# PowerSupply.net
KiCad netlist of a schematic drawn in Altium Designer
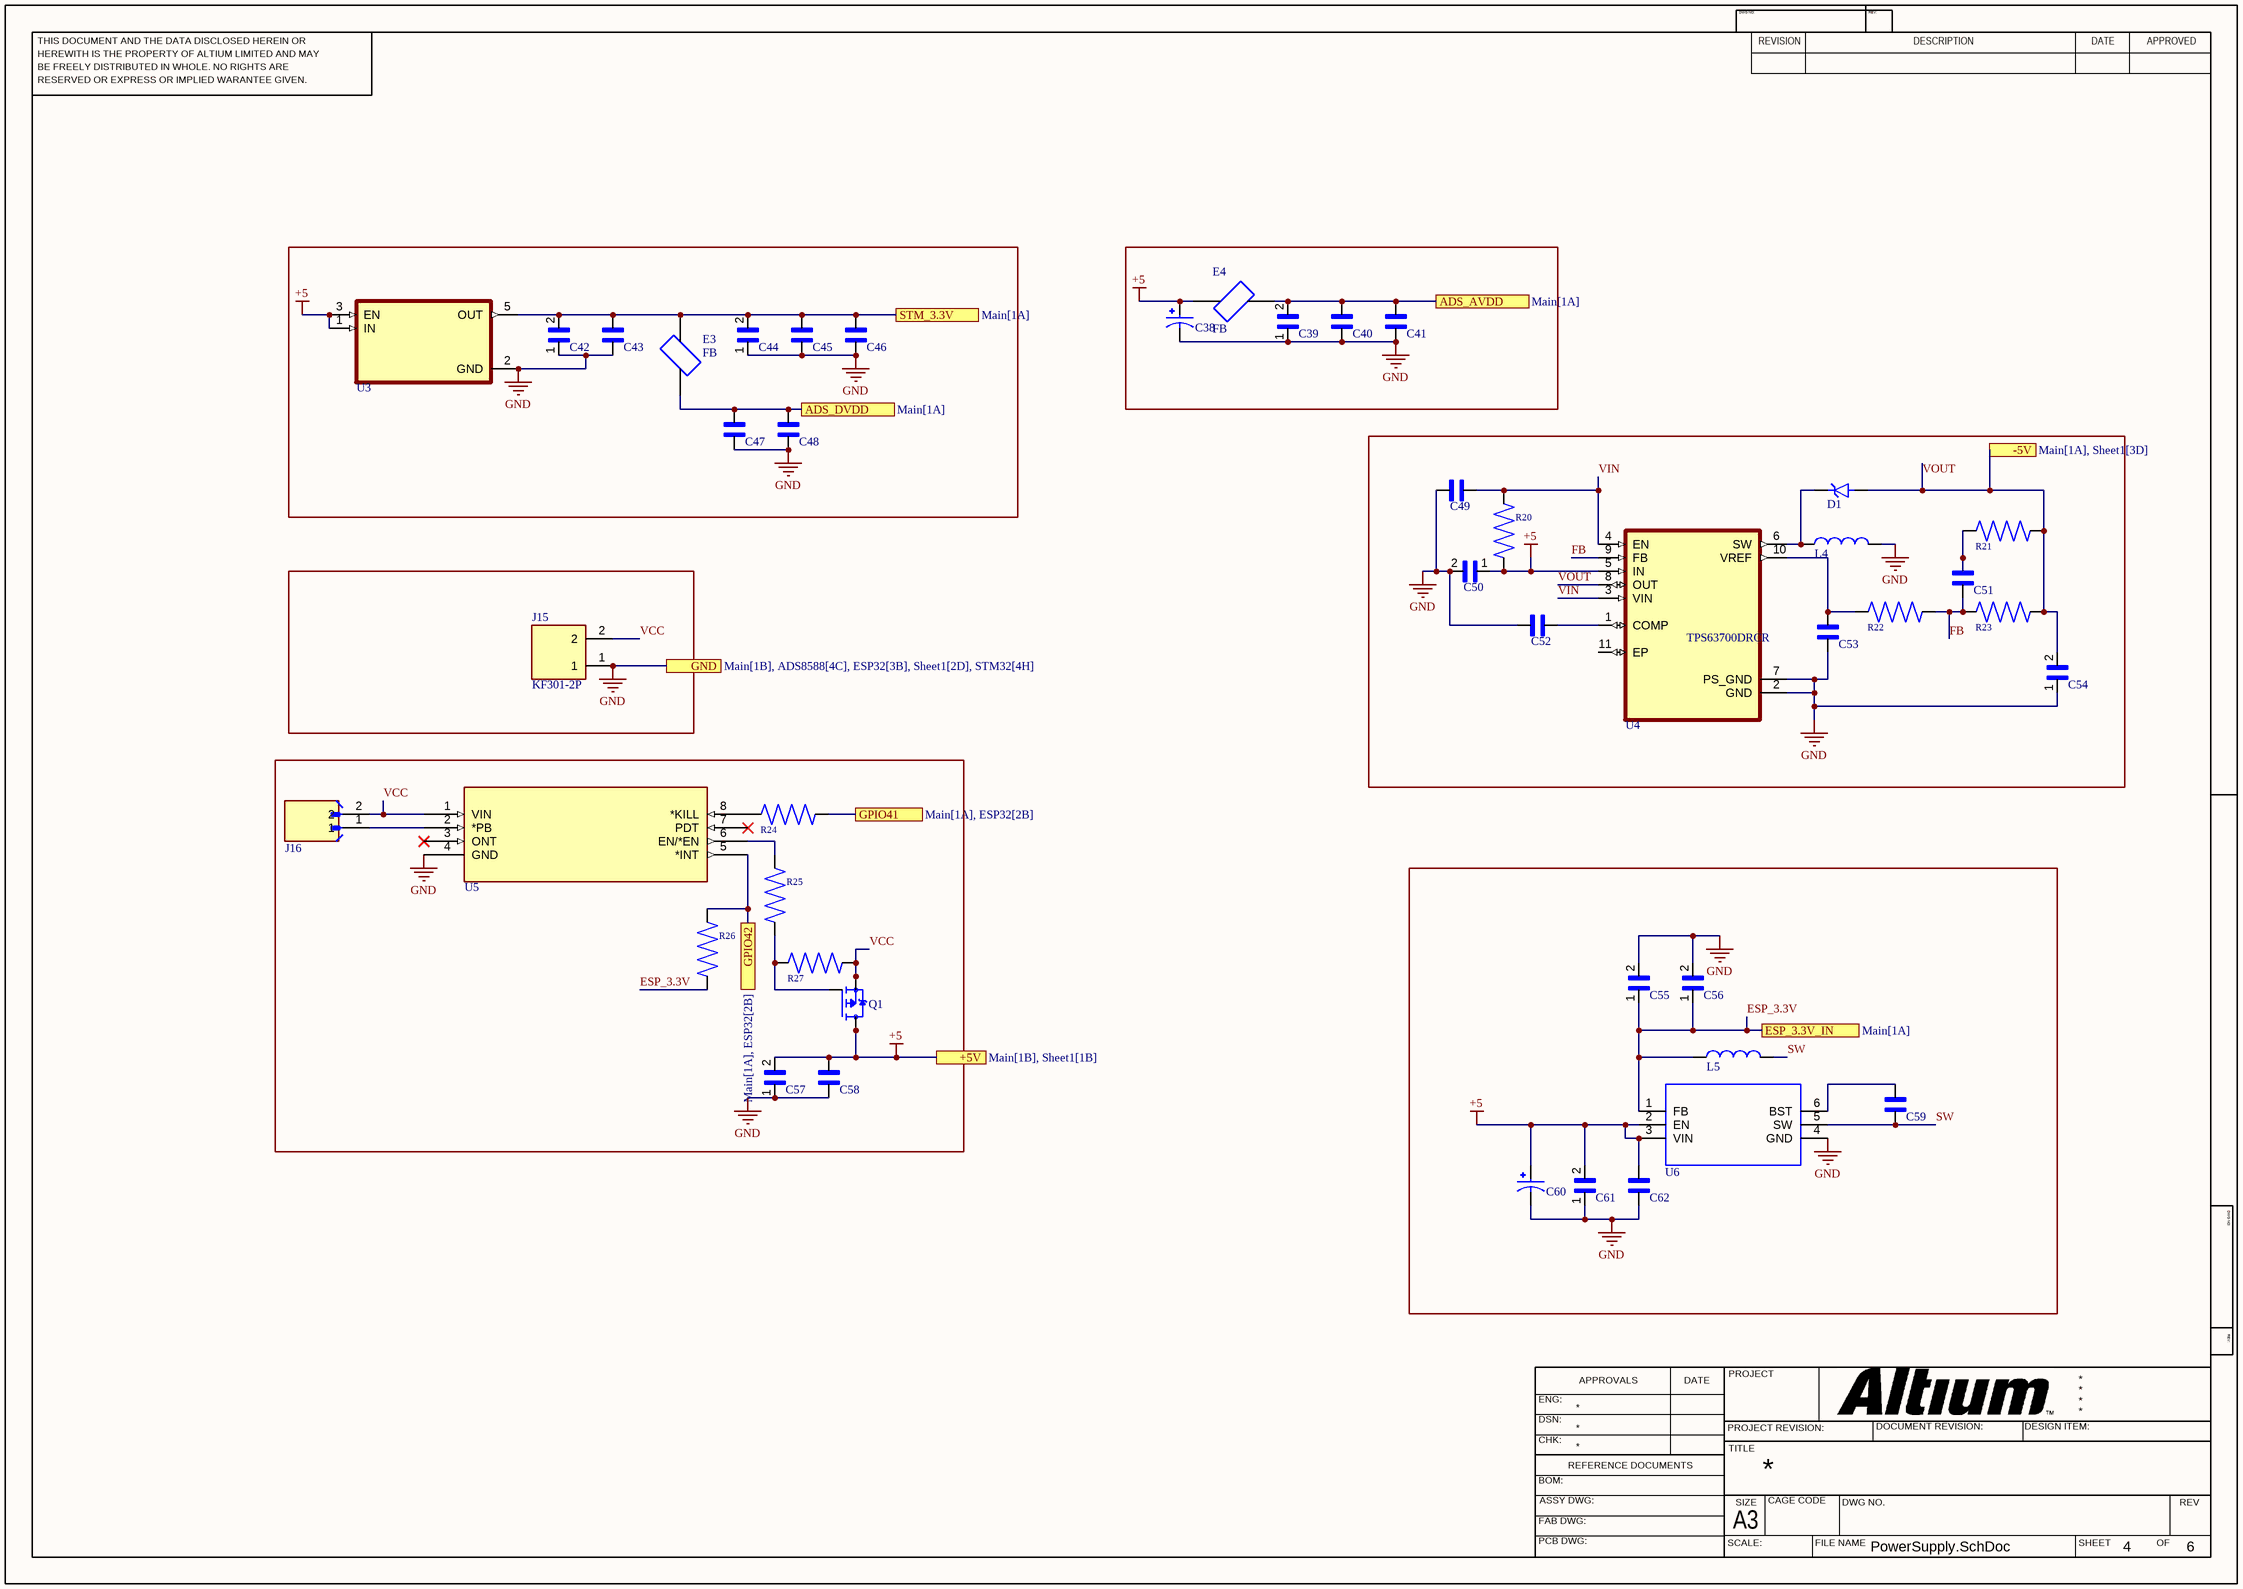
[diagram p0: PowerSupply.SchDoc]

(export (version "E")
  (design (tool "Eeschema 10.0.6"))
  (components
    (comp (ref "C38")
      (value "100 uF")
      (footprint "100 uF")
      (fields (field (name "MF") "Panasonic") (field (name "MP") "16SVPG100M"))
      (libsource (lib "ESP32-S3-WROOM-1-N16R8") (part "100 uF"))
    )
    (comp (ref "C39")
      (value "C2012X7R1H104K085AA")
      (footprint "CAPC2012X100N")
      (description "0.1 ÂµF Â±10% 50V Ceramic Capacitor X7R 0805 (2012 Metric)")
      (fields (field (name "MF") "TDK") (field (name "DIGI-KEY_PART_NUMBER") "445-7534-1-ND"))
      (libsource (lib "ESP32-S3-WROOM-1-N16R8") (part "C2012X7R1H104K085AA"))
    )
    (comp (ref "C40")
      (value "CAP603")
      (footprint "CAP603")
      (description "0.1 ÂµF Â±5% 10V Ceramic Capacitor X7R 0603 (1608 Metric)")
      (fields (field (name "MF") "Vishay") (field (name "MP") "VJ0603Y104JXQCW1BC"))
      (libsource (lib "ESP32-S3-WROOM-1-N16R8") (part "CAP603"))
    )
    (comp (ref "C41")
      (value "CAP603")
      (footprint "CAP603")
      (description "0.1 ÂµF Â±5% 10V Ceramic Capacitor X7R 0603 (1608 Metric)")
      (fields (field (name "MF") "Vishay") (field (name "MP") "VJ0603Y104JXQCW1BC"))
      (libsource (lib "ESP32-S3-WROOM-1-N16R8") (part "CAP603"))
    )
    (comp (ref "C42")
      (value "C2012X7R1H104K085AA")
      (footprint "CAPC2012X100N")
      (description "0.1 ÂµF Â±10% 50V Ceramic Capacitor X7R 0805 (2012 Metric)")
      (fields (field (name "MF") "TDK") (field (name "DIGI-KEY_PART_NUMBER") "445-7534-1-ND"))
      (libsource (lib "ESP32-S3-WROOM-1-N16R8") (part "C2012X7R1H104K085AA"))
    )
    (comp (ref "C43")
      (value "CAP603")
      (footprint "CAP603")
      (description "0.1 ÂµF Â±5% 10V Ceramic Capacitor X7R 0603 (1608 Metric)")
      (fields (field (name "MF") "Vishay") (field (name "MP") "VJ0603Y104JXQCW1BC"))
      (libsource (lib "ESP32-S3-WROOM-1-N16R8") (part "CAP603"))
    )
    (comp (ref "C44")
      (value "C2012X7R1H104K085AA")
      (footprint "CAPC2012X100N")
      (description "0.1 ÂµF Â±10% 50V Ceramic Capacitor X7R 0805 (2012 Metric)")
      (fields (field (name "MF") "TDK") (field (name "DIGI-KEY_PART_NUMBER") "445-7534-1-ND"))
      (libsource (lib "ESP32-S3-WROOM-1-N16R8") (part "C2012X7R1H104K085AA"))
    )
    (comp (ref "C45")
      (value "CAP603")
      (footprint "CAP603")
      (description "0.1 ÂµF Â±5% 10V Ceramic Capacitor X7R 0603 (1608 Metric)")
      (fields (field (name "MF") "Vishay") (field (name "MP") "VJ0603Y104JXQCW1BC"))
      (libsource (lib "ESP32-S3-WROOM-1-N16R8") (part "CAP603"))
    )
    (comp (ref "C46")
      (value "CAP603")
      (footprint "CAP603")
      (description "0.1 ÂµF Â±5% 10V Ceramic Capacitor X7R 0603 (1608 Metric)")
      (fields (field (name "MF") "Vishay") (field (name "MP") "VJ0603Y104JXQCW1BC"))
      (libsource (lib "ESP32-S3-WROOM-1-N16R8") (part "CAP603"))
    )
    (comp (ref "C47")
      (value "CAP603")
      (footprint "CAP603")
      (description "0.1 ÂµF Â±5% 10V Ceramic Capacitor X7R 0603 (1608 Metric)")
      (fields (field (name "MF") "Vishay") (field (name "MP") "VJ0603Y104JXQCW1BC"))
      (libsource (lib "ESP32-S3-WROOM-1-N16R8") (part "CAP603"))
    )
    (comp (ref "C48")
      (value "CAP603")
      (footprint "CAP603")
      (description "0.1 ÂµF Â±5% 10V Ceramic Capacitor X7R 0603 (1608 Metric)")
      (fields (field (name "MF") "Vishay") (field (name "MP") "VJ0603Y104JXQCW1BC"))
      (libsource (lib "ESP32-S3-WROOM-1-N16R8") (part "CAP603"))
    )
    (comp (ref "C49")
      (value "CAP603")
      (footprint "CAP603")
      (description "0.1 ÂµF Â±5% 10V Ceramic Capacitor X7R 0603 (1608 Metric)")
      (fields (field (name "MF") "Vishay") (field (name "MP") "VJ0603Y104JXQCW1BC"))
      (libsource (lib "") (part "CAP603_1"))
    )
    (comp (ref "C50")
      (value "C2012X7R1H104K085AA")
      (footprint "CAPC2012X100N")
      (description "0.1 ÂµF Â±10% 50V Ceramic Capacitor X7R 0805 (2012 Metric)")
      (fields (field (name "MF") "TDK") (field (name "DIGI-KEY_PART_NUMBER") "445-7534-1-ND"))
      (libsource (lib "") (part "C2012X7R1H104K085AA_1"))
    )
    (comp (ref "C51")
      (value "CAP603")
      (footprint "CAP603")
      (description "0.1 ÂµF Â±5% 10V Ceramic Capacitor X7R 0603 (1608 Metric)")
      (fields (field (name "MF") "Vishay") (field (name "MP") "VJ0603Y104JXQCW1BC"))
      (libsource (lib "ESP32-S3-WROOM-1-N16R8") (part "CAP603"))
    )
    (comp (ref "C52")
      (value "CAP603")
      (footprint "CAP603")
      (description "0.1 ÂµF Â±5% 10V Ceramic Capacitor X7R 0603 (1608 Metric)")
      (fields (field (name "MF") "Vishay") (field (name "MP") "VJ0603Y104JXQCW1BC"))
      (libsource (lib "") (part "CAP603_1"))
    )
    (comp (ref "C53")
      (value "CAP603")
      (footprint "CAP603")
      (description "0.1 ÂµF Â±5% 10V Ceramic Capacitor X7R 0603 (1608 Metric)")
      (fields (field (name "MF") "Vishay") (field (name "MP") "VJ0603Y104JXQCW1BC"))
      (libsource (lib "ESP32-S3-WROOM-1-N16R8") (part "CAP603"))
    )
    (comp (ref "C54")
      (value "C2012X7R1H104K085AA")
      (footprint "CAPC2012X100N")
      (description "0.1 ÂµF Â±10% 50V Ceramic Capacitor X7R 0805 (2012 Metric)")
      (fields (field (name "MF") "TDK") (field (name "DIGI-KEY_PART_NUMBER") "445-7534-1-ND"))
      (libsource (lib "ESP32-S3-WROOM-1-N16R8") (part "C2012X7R1H104K085AA"))
    )
    (comp (ref "C55")
      (value "C2012X7R1H104K085AA")
      (footprint "CAPC2012X100N")
      (description "0.1 ÂµF Â±10% 50V Ceramic Capacitor X7R 0805 (2012 Metric)")
      (fields (field (name "MF") "TDK") (field (name "DIGI-KEY_PART_NUMBER") "445-7534-1-ND"))
      (libsource (lib "ESP32-S3-WROOM-1-N16R8") (part "C2012X7R1H104K085AA"))
    )
    (comp (ref "C56")
      (value "C2012X7R1H104K085AA")
      (footprint "CAPC2012X100N")
      (description "0.1 ÂµF Â±10% 50V Ceramic Capacitor X7R 0805 (2012 Metric)")
      (fields (field (name "MF") "TDK") (field (name "DIGI-KEY_PART_NUMBER") "445-7534-1-ND"))
      (libsource (lib "ESP32-S3-WROOM-1-N16R8") (part "C2012X7R1H104K085AA"))
    )
    (comp (ref "C57")
      (value "C2012X7R1H104K085AA")
      (footprint "CAPC2012X100N")
      (description "0.1 ÂµF Â±10% 50V Ceramic Capacitor X7R 0805 (2012 Metric)")
      (fields (field (name "MF") "TDK") (field (name "DIGI-KEY_PART_NUMBER") "445-7534-1-ND"))
      (libsource (lib "ESP32-S3-WROOM-1-N16R8") (part "C2012X7R1H104K085AA"))
    )
    (comp (ref "C58")
      (value "CAP603")
      (footprint "CAP603")
      (description "0.1 ÂµF Â±5% 10V Ceramic Capacitor X7R 0603 (1608 Metric)")
      (fields (field (name "MF") "Vishay") (field (name "MP") "VJ0603Y104JXQCW1BC"))
      (libsource (lib "ESP32-S3-WROOM-1-N16R8") (part "CAP603"))
    )
    (comp (ref "C59")
      (value "CAP603")
      (footprint "CAP603")
      (description "0.1 ÂµF Â±5% 10V Ceramic Capacitor X7R 0603 (1608 Metric)")
      (fields (field (name "MF") "Vishay") (field (name "MP") "VJ0603Y104JXQCW1BC"))
      (libsource (lib "ESP32-S3-WROOM-1-N16R8") (part "CAP603"))
    )
    (comp (ref "C60")
      (value "100 uF")
      (footprint "100 uF")
      (fields (field (name "MF") "Panasonic") (field (name "MP") "16SVPG100M"))
      (libsource (lib "ESP32-S3-WROOM-1-N16R8") (part "100 uF"))
    )
    (comp (ref "C61")
      (value "C2012X7R1H104K085AA")
      (footprint "CAPC2012X100N")
      (description "0.1 ÂµF Â±10% 50V Ceramic Capacitor X7R 0805 (2012 Metric)")
      (fields (field (name "MF") "TDK") (field (name "DIGI-KEY_PART_NUMBER") "445-7534-1-ND"))
      (libsource (lib "ESP32-S3-WROOM-1-N16R8") (part "C2012X7R1H104K085AA"))
    )
    (comp (ref "C62")
      (value "CAP603")
      (footprint "CAP603")
      (description "0.1 ÂµF Â±5% 10V Ceramic Capacitor X7R 0603 (1608 Metric)")
      (fields (field (name "MF") "Vishay") (field (name "MP") "VJ0603Y104JXQCW1BC"))
      (libsource (lib "ESP32-S3-WROOM-1-N16R8") (part "CAP603"))
    )
    (comp (ref "D1")
      (value "zenor diode")
      (footprint "zenor diode")
      (description "DO-214AC (SMA), 1250mW, 5%, Zener Diode")
      (fields (field (name "MF") "Taiwan Semiconductor") (field (name "MP") "1SMA4746H"))
      (libsource (lib "ESP32-S3-WROOM-1-N16R8") (part "zenor diode"))
    )
    (comp (ref "E3")
      (value "FB")
      (footprint "FB_MI1206K601R-10")
      (description "600 Ohms @ 100 MHz 1 Power, Signal Line Ferrite Bead 1206 (3216 Metric) 1.5A 80mOhm")
      (fields (field (name "MF") "Laird-Signal Integrity") (field (name "MP") "MI1206K601R-10"))
      (libsource (lib "Schlib1") (part "MI1206K601R-10"))
    )
    (comp (ref "E4")
      (value "FB")
      (footprint "FB_MI1206K601R-10")
      (description "600 Ohms @ 100 MHz 1 Power, Signal Line Ferrite Bead 1206 (3216 Metric) 1.5A 80mOhm")
      (fields (field (name "MF") "Laird-Signal Integrity") (field (name "MP") "MI1206K601R-10"))
      (libsource (lib "Schlib1") (part "MI1206K601R-10"))
    )
    (comp (ref "J15")
      (value "KF301-2P")
      (footprint "HANDSON_KF301-2P")
      (description "2 Pin Terminal Block 5mm Pitch")
      (fields (field (name "MF") "Handson Technology"))
      (libsource (lib "Schlib1") (part "KF301-2P"))
    )
    (comp (ref "J16")
      (value "2-pin jst")
      (footprint "2-pin jst")
      (description "Connector Header Through Hole 2 position 0.079 (2.00mm)")
      (fields (field (name "MF") "JST Sales America Inc.") (field (name "MP") "B2B-PH-K-S"))
      (libsource (lib "ESP32-S3-WROOM-1-N16R8") (part "2-pin jst"))
    )
    (comp (ref "L4")
      (value "inductor")
      (footprint "inductor")
      (description "Inductor with Inductance: 4.7uH Tol. +/-20%, Package: 0603 _1608_")
      (fields (field (name "MF") "Murata Electronics") (field (name "MP") "LQM18PN4R7MFRL"))
      (libsource (lib "ESP32-S3-WROOM-1-N16R8") (part "inductor"))
    )
    (comp (ref "L5")
      (value "inductor")
      (footprint "inductor")
      (description "Inductor with Inductance: 4.7uH Tol. +/-20%, Package: 0603 _1608_")
      (fields (field (name "MF") "Murata Electronics") (field (name "MP") "LQM18PN4R7MFRL"))
      (libsource (lib "ESP32-S3-WROOM-1-N16R8") (part "inductor"))
    )
    (comp (ref "Q1")
      (value "AO4407A")
      (footprint "AO4407A")
      (description "P-Channel 30 V 12A (Ta) 3.1W (Ta) Surface Mount 8-SOIC")
      (fields (field (name "MF") "Alpha &"))
      (libsource (lib "ESP32-S3-WROOM-1-N16R8") (part "AO4407A"))
    )
    (comp (ref "R20")
      (value "RES-603")
      (footprint "CAP603")
      (fields (field (name "MF") "Yageo") (field (name "MP") "RC0805FR-0710KL"))
      (libsource (lib "ESP32-S3-WROOM-1-N16R8") (part "RES-603"))
    )
    (comp (ref "R21")
      (value "RES-603")
      (footprint "CAP603")
      (fields (field (name "MF") "Yageo") (field (name "MP") "RC0805FR-0710KL"))
      (libsource (lib "ESP32-S3-WROOM-1-N16R8") (part "RES-603"))
    )
    (comp (ref "R22")
      (value "RES-603")
      (footprint "CAP603")
      (fields (field (name "MF") "Yageo") (field (name "MP") "RC0805FR-0710KL"))
      (libsource (lib "ESP32-S3-WROOM-1-N16R8") (part "RES-603"))
    )
    (comp (ref "R23")
      (value "RES-603")
      (footprint "CAP603")
      (fields (field (name "MF") "Yageo") (field (name "MP") "RC0805FR-0710KL"))
      (libsource (lib "ESP32-S3-WROOM-1-N16R8") (part "RES-603"))
    )
    (comp (ref "R24")
      (value "RES-603")
      (footprint "CAP603")
      (fields (field (name "MF") "Yageo") (field (name "MP") "RC0805FR-0710KL"))
      (libsource (lib "ESP32-S3-WROOM-1-N16R8") (part "RES-603"))
    )
    (comp (ref "R25")
      (value "RES-603")
      (footprint "CAP603")
      (fields (field (name "MF") "Yageo") (field (name "MP") "RC0805FR-0710KL"))
      (libsource (lib "ESP32-S3-WROOM-1-N16R8") (part "RES-603"))
    )
    (comp (ref "R26")
      (value "RES-603")
      (footprint "CAP603")
      (fields (field (name "MF") "Yageo") (field (name "MP") "RC0805FR-0710KL"))
      (libsource (lib "ESP32-S3-WROOM-1-N16R8") (part "RES-603"))
    )
    (comp (ref "R27")
      (value "RES-603")
      (footprint "CAP603")
      (fields (field (name "MF") "Yageo") (field (name "MP") "RC0805FR-0710KL"))
      (libsource (lib "ESP32-S3-WROOM-1-N16R8") (part "RES-603"))
    )
    (comp (ref "U3")
      (value "TLV75533PDBVR")
      (footprint "TLV75533PDBVR")
      (description "500-mA High-PSRR Low-IQ-Tief-Dropout-Spannungsregler mitablem")
      (fields (field (name "MF") "Texas Instruments"))
      (libsource (lib "ESP32-S3-WROOM-1-N16R8") (part "TLV75533PDBVR"))
    )
    (comp (ref "U4")
      (value "TPS63700DRCR")
      (footprint "TPS63700DRCR")
      (description "Adjustable, -15V Output Inverting DC/DC Converter in 3x3 QFN")
      (fields (field (name "MF") "Texas Instruments"))
      (libsource (lib "ESP32-S3-WROOM-1-N16R8") (part "TPS63700DRCR"))
    )
    (comp (ref "U5")
      (value "LTC2954CTS8-1#TRMPBF")
      (footprint "LTC2954CTS8-1#TRMPBF")
      (fields (field (name "MF") "{'manufacturer': u'Analog Devices Inc.'}"))
      (libsource (lib "ESP32-S3-WROOM-1-N16R8") (part "LTC2954CTS8-1#TRMPBF"))
    )
    (comp (ref "U6")
      (value "AP63203WU-7")
      (footprint "AP63203WU-7")
      (description "Buck Switching Regulator IC Positive Fixed 3.3V 1 Output 2A SOT-23-6 Thin, TSOT-23-6")
      (fields (field (name "MF") "Diodes Zetex"))
      (libsource (lib "ESP32-S3-WROOM-1-N16R8") (part "AP63203WU-7"))
    )
  )
  (nets
    (net (code "1") (name "+5") (class "Default")
      (node (ref "C38") (pin "1") (pinfunction "1_1") (pintype "passive"))
      (node (ref "C50") (pin "1") (pinfunction "1_1") (pintype "passive"))
      (node (ref "C57") (pin "2") (pinfunction "2_2") (pintype "passive"))
      (node (ref "C58") (pin "2") (pinfunction "2_2") (pintype "passive"))
      (node (ref "C60") (pin "1") (pinfunction "1_1") (pintype "passive"))
      (node (ref "C61") (pin "2") (pinfunction "2_2") (pintype "passive"))
      (node (ref "C62") (pin "2") (pinfunction "2_2") (pintype "passive"))
      (node (ref "E4") (pin "2") (pinfunction "2_2") (pintype "passive"))
      (node (ref "Q1") (pin "5") (pinfunction "D_5") (pintype "passive"))
      (node (ref "Q1") (pin "6") (pinfunction "D_6") (pintype "passive"))
      (node (ref "Q1") (pin "7") (pinfunction "D_7") (pintype "passive"))
      (node (ref "Q1") (pin "8") (pinfunction "D_8") (pintype "passive"))
      (node (ref "R20") (pin "1") (pinfunction "1_1") (pintype "passive"))
      (node (ref "U3") (pin "1") (pinfunction "IN_1") (pintype "input"))
      (node (ref "U3") (pin "3") (pinfunction "EN_3") (pintype "input"))
      (node (ref "U4") (pin "5") (pinfunction "IN_5") (pintype "input"))
      (node (ref "U6") (pin "2") (pinfunction "EN_2") (pintype "passive"))
      (node (ref "U6") (pin "3") (pinfunction "VIN_3") (pintype "passive"))
    )
    (net (code "2") (name "/ADS_AVDD") (class "Default")
      (node (ref "C39") (pin "2") (pinfunction "2_2") (pintype "passive"))
      (node (ref "C40") (pin "2") (pinfunction "2_2") (pintype "passive"))
      (node (ref "C41") (pin "2") (pinfunction "2_2") (pintype "passive"))
      (node (ref "E4") (pin "1") (pinfunction "1_1") (pintype "passive"))
    )
    (net (code "3") (name "/ADS_DVDD") (class "Default")
      (node (ref "C47") (pin "2") (pinfunction "2_2") (pintype "passive"))
      (node (ref "C48") (pin "2") (pinfunction "2_2") (pintype "passive"))
      (node (ref "E3") (pin "1") (pinfunction "1_1") (pintype "passive"))
    )
    (net (code "4") (name "/ESP_3.3V") (class "Default")
      (node (ref "C55") (pin "1") (pinfunction "1_1") (pintype "passive"))
      (node (ref "C56") (pin "1") (pinfunction "1_1") (pintype "passive"))
      (node (ref "L5") (pin "1") (pinfunction "1_1") (pintype "passive"))
      (node (ref "R26") (pin "1") (pinfunction "1_1") (pintype "passive"))
      (node (ref "U6") (pin "1") (pinfunction "FB_1") (pintype "passive"))
    )
    (net (code "5") (name "/FB") (class "Default")
      (node (ref "C51") (pin "1") (pinfunction "1_1") (pintype "passive"))
      (node (ref "R22") (pin "2") (pinfunction "2_2") (pintype "passive"))
      (node (ref "R23") (pin "1") (pinfunction "1_1") (pintype "passive"))
      (node (ref "U4") (pin "9") (pinfunction "FB_9") (pintype "input"))
    )
    (net (code "6") (name "/GPIO41") (class "Default")
      (node (ref "R24") (pin "2") (pinfunction "2_2") (pintype "passive"))
    )
    (net (code "7") (name "/GPIO42") (class "Default")
      (node (ref "R26") (pin "2") (pinfunction "2_2") (pintype "passive"))
      (node (ref "U5") (pin "5") (pinfunction "*INT_5") (pintype "output"))
    )
    (net (code "8") (name "/STM_3.3V") (class "Default")
      (node (ref "C42") (pin "2") (pinfunction "2_2") (pintype "passive"))
      (node (ref "C43") (pin "2") (pinfunction "2_2") (pintype "passive"))
      (node (ref "C44") (pin "2") (pinfunction "2_2") (pintype "passive"))
      (node (ref "C45") (pin "2") (pinfunction "2_2") (pintype "passive"))
      (node (ref "C46") (pin "2") (pinfunction "2_2") (pintype "passive"))
      (node (ref "E3") (pin "2") (pinfunction "2_2") (pintype "passive"))
      (node (ref "U3") (pin "5") (pinfunction "OUT_5") (pintype "output"))
    )
    (net (code "9") (name "/SW") (class "Default")
      (node (ref "C59") (pin "1") (pinfunction "1_1") (pintype "passive"))
      (node (ref "L5") (pin "2") (pinfunction "2_2") (pintype "passive"))
      (node (ref "U6") (pin "5") (pinfunction "SW_5") (pintype "passive"))
    )
    (net (code "10") (name "/VCC") (class "Default")
      (node (ref "J15") (pin "2") (pinfunction "2_2") (pintype "passive"))
      (node (ref "J16") (pin "2") (pinfunction "2_2") (pintype "passive"))
      (node (ref "Q1") (pin "1") (pinfunction "S_1") (pintype "passive"))
      (node (ref "Q1") (pin "2") (pinfunction "S_2") (pintype "passive"))
      (node (ref "Q1") (pin "3") (pinfunction "S_3") (pintype "passive"))
      (node (ref "R27") (pin "2") (pinfunction "2_2") (pintype "passive"))
      (node (ref "U5") (pin "1") (pinfunction "VIN_1") (pintype "input"))
    )
    (net (code "11") (name "/VIN") (class "Default")
      (node (ref "C49") (pin "1") (pinfunction "1_1") (pintype "passive"))
      (node (ref "R20") (pin "2") (pinfunction "2_2") (pintype "passive"))
      (node (ref "U4") (pin "3") (pinfunction "VIN_3") (pintype "input"))
      (node (ref "U4") (pin "4") (pinfunction "EN_4") (pintype "input"))
    )
    (net (code "12") (name "/VOUT") (class "Default")
      (node (ref "C54") (pin "2") (pinfunction "2_2") (pintype "passive"))
      (node (ref "D1") (pin "A") (pinfunction "A_A") (pintype "passive"))
      (node (ref "R21") (pin "2") (pinfunction "2_2") (pintype "passive"))
      (node (ref "R23") (pin "2") (pinfunction "2_2") (pintype "passive"))
      (node (ref "U4") (pin "8") (pinfunction "OUT_8") (pintype "bidirectional"))
    )
    (net (code "13") (name "GND") (class "Default")
      (node (ref "C38") (pin "2") (pinfunction "2_2") (pintype "passive"))
      (node (ref "C39") (pin "1") (pinfunction "1_1") (pintype "passive"))
      (node (ref "C40") (pin "1") (pinfunction "1_1") (pintype "passive"))
      (node (ref "C41") (pin "1") (pinfunction "1_1") (pintype "passive"))
      (node (ref "C42") (pin "1") (pinfunction "1_1") (pintype "passive"))
      (node (ref "C43") (pin "1") (pinfunction "1_1") (pintype "passive"))
      (node (ref "C44") (pin "1") (pinfunction "1_1") (pintype "passive"))
      (node (ref "C45") (pin "1") (pinfunction "1_1") (pintype "passive"))
      (node (ref "C46") (pin "1") (pinfunction "1_1") (pintype "passive"))
      (node (ref "C47") (pin "1") (pinfunction "1_1") (pintype "passive"))
      (node (ref "C48") (pin "1") (pinfunction "1_1") (pintype "passive"))
      (node (ref "C49") (pin "2") (pinfunction "2_2") (pintype "passive"))
      (node (ref "C50") (pin "2") (pinfunction "2_2") (pintype "passive"))
      (node (ref "C52") (pin "2") (pinfunction "2_2") (pintype "passive"))
      (node (ref "C53") (pin "1") (pinfunction "1_1") (pintype "passive"))
      (node (ref "C54") (pin "1") (pinfunction "1_1") (pintype "passive"))
      (node (ref "C55") (pin "2") (pinfunction "2_2") (pintype "passive"))
      (node (ref "C56") (pin "2") (pinfunction "2_2") (pintype "passive"))
      (node (ref "C57") (pin "1") (pinfunction "1_1") (pintype "passive"))
      (node (ref "C58") (pin "1") (pinfunction "1_1") (pintype "passive"))
      (node (ref "C60") (pin "2") (pinfunction "2_2") (pintype "passive"))
      (node (ref "C61") (pin "1") (pinfunction "1_1") (pintype "passive"))
      (node (ref "C62") (pin "1") (pinfunction "1_1") (pintype "passive"))
      (node (ref "J15") (pin "1") (pinfunction "1_1") (pintype "passive"))
      (node (ref "L4") (pin "2") (pinfunction "2_2") (pintype "passive"))
      (node (ref "U3") (pin "2") (pinfunction "GND_2") (pintype "power_in"))
      (node (ref "U4") (pin "2") (pinfunction "GND_2") (pintype "power_in"))
      (node (ref "U4") (pin "7") (pinfunction "PS_GND_7") (pintype "power_in"))
      (node (ref "U5") (pin "4") (pinfunction "GND_4") (pintype "power_in"))
      (node (ref "U6") (pin "4") (pinfunction "GND_4") (pintype "passive"))
    )
    (net (code "14") (name "Net-(C51-Pad2)") (class "Default")
      (node (ref "C51") (pin "2") (pinfunction "2_2") (pintype "passive"))
      (node (ref "R21") (pin "1") (pinfunction "1_1") (pintype "passive"))
    )
    (net (code "15") (name "Net-(D1-K)") (class "Default")
      (node (ref "D1") (pin "C") (pinfunction "K_C") (pintype "passive"))
      (node (ref "L4") (pin "1") (pinfunction "1_1") (pintype "passive"))
      (node (ref "U4") (pin "6") (pinfunction "SW_6") (pintype "output"))
    )
    (net (code "16") (name "Net-(Q1-G)") (class "Default")
      (node (ref "Q1") (pin "4") (pinfunction "G_4") (pintype "passive"))
      (node (ref "R25") (pin "2") (pinfunction "2_2") (pintype "passive"))
      (node (ref "R27") (pin "1") (pinfunction "1_1") (pintype "passive"))
    )
    (net (code "17") (name "Net-(U4-COMP)") (class "Default")
      (node (ref "C52") (pin "1") (pinfunction "1_1") (pintype "passive"))
      (node (ref "U4") (pin "1") (pinfunction "COMP_1") (pintype "bidirectional"))
    )
    (net (code "18") (name "Net-(U4-VREF)") (class "Default")
      (node (ref "C53") (pin "2") (pinfunction "2_2") (pintype "passive"))
      (node (ref "R22") (pin "1") (pinfunction "1_1") (pintype "passive"))
      (node (ref "U4") (pin "10") (pinfunction "VREF_10") (pintype "output"))
    )
    (net (code "19") (name "Net-(U5-*KILL)") (class "Default")
      (node (ref "R24") (pin "1") (pinfunction "1_1") (pintype "passive"))
      (node (ref "U5") (pin "8") (pinfunction "*KILL_8") (pintype "input"))
    )
    (net (code "20") (name "Net-(U5-*PB)") (class "Default")
      (node (ref "J16") (pin "1") (pinfunction "1_1") (pintype "passive"))
      (node (ref "U5") (pin "2") (pinfunction "*PB_2") (pintype "input"))
    )
    (net (code "21") (name "Net-(U5-EN{slash}*EN)") (class "Default")
      (node (ref "R25") (pin "1") (pinfunction "1_1") (pintype "passive"))
      (node (ref "U5") (pin "6") (pinfunction "EN/*EN_6") (pintype "output"))
    )
    (net (code "22") (name "Net-(U6-BST)") (class "Default")
      (node (ref "C59") (pin "2") (pinfunction "2_2") (pintype "passive"))
      (node (ref "U6") (pin "6") (pinfunction "BST_6") (pintype "passive"))
    )
    (net (code "23") (name "unconnected-(U4-EP-Pad11)") (class "Default")
      (node (ref "U4") (pin "11") (pinfunction "EP_11") (pintype "bidirectional"))
    )
    (net (code "24") (name "unconnected-(U5-ONT-Pad3)") (class "Default")
      (node (ref "U5") (pin "3") (pinfunction "ONT_3") (pintype "input+no_connect"))
    )
    (net (code "25") (name "unconnected-(U5-PDT-Pad7)") (class "Default")
      (node (ref "U5") (pin "7") (pinfunction "PDT_7") (pintype "input+no_connect"))
    )
  )
)
